# V2LinearArray.net
KiCad netlist of a schematic drawn in Altium Designer
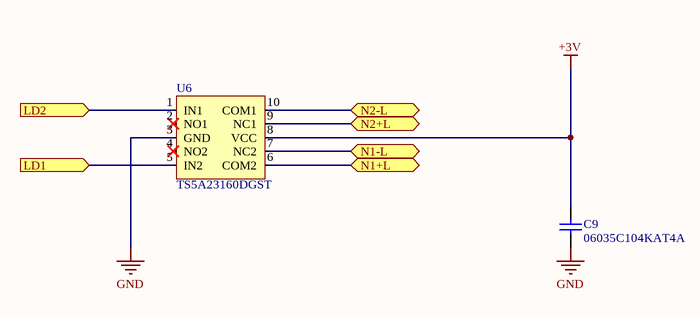
[diagram p0: V2LinearArray.SchDoc]

(export (version "E")
  (design (tool "Eeschema 10.0.6"))
  (components
    (comp (ref "C9")
      (value "06035C104KAT4A")
      (footprint "CAPC1608X90X35LL15T15")
      (fields (field (name "MANUFACTURER") "AVX Interconnect / Elco"))
      (libsource (lib "Altium Content Vault") (part "CAP"))
    )
    (comp (ref "U6")
      (value "TS5A23160DGST")
      (footprint "TSSOP50P490X110-10N")
      (description "0.9-Ω on-state resistance, 5-V, 2: 1 (SPDT), 2-channel analog switch 10-VSSOP -40 to 85")
      (libsource (lib "Nick") (part "TS5A23160DGST-Symbol-1"))
    )
  )
  (nets
    (net (code "1") (name "+3V") (class "Default")
      (node (ref "C9") (pin "1") (pinfunction "1_1") (pintype "passive"))
      (node (ref "U6") (pin "8") (pinfunction "VCC_8") (pintype "power_in"))
    )
    (net (code "2") (name "/LD1") (class "Default")
      (node (ref "U6") (pin "5") (pinfunction "IN2_5") (pintype "input"))
    )
    (net (code "3") (name "/LD2") (class "Default")
      (node (ref "U6") (pin "1") (pinfunction "IN1_1") (pintype "input"))
    )
    (net (code "4") (name "/N1+L") (class "Default")
      (node (ref "U6") (pin "6") (pinfunction "COM2_6") (pintype "bidirectional"))
    )
    (net (code "5") (name "/N1-L") (class "Default")
      (node (ref "U6") (pin "7") (pinfunction "NC2_7") (pintype "bidirectional"))
    )
    (net (code "6") (name "/N2+L") (class "Default")
      (node (ref "U6") (pin "9") (pinfunction "NC1_9") (pintype "bidirectional"))
    )
    (net (code "7") (name "/N2-L") (class "Default")
      (node (ref "U6") (pin "10") (pinfunction "COM1_10") (pintype "bidirectional"))
    )
    (net (code "8") (name "GND") (class "Default")
      (node (ref "C9") (pin "2") (pinfunction "2_2") (pintype "passive"))
      (node (ref "U6") (pin "3") (pinfunction "GND_3") (pintype "power_in"))
    )
    (net (code "9") (name "unconnected-(U6-NO1-Pad2)") (class "Default")
      (node (ref "U6") (pin "2") (pinfunction "NO1_2") (pintype "bidirectional+no_connect"))
    )
    (net (code "10") (name "unconnected-(U6-NO2-Pad4)") (class "Default")
      (node (ref "U6") (pin "4") (pinfunction "NO2_4") (pintype "bidirectional+no_connect"))
    )
  )
)
